# Adafruit_HUZZAH_ESP8266_Basic_Breakout.net
KiCad netlist of a schematic drawn in EAGLE
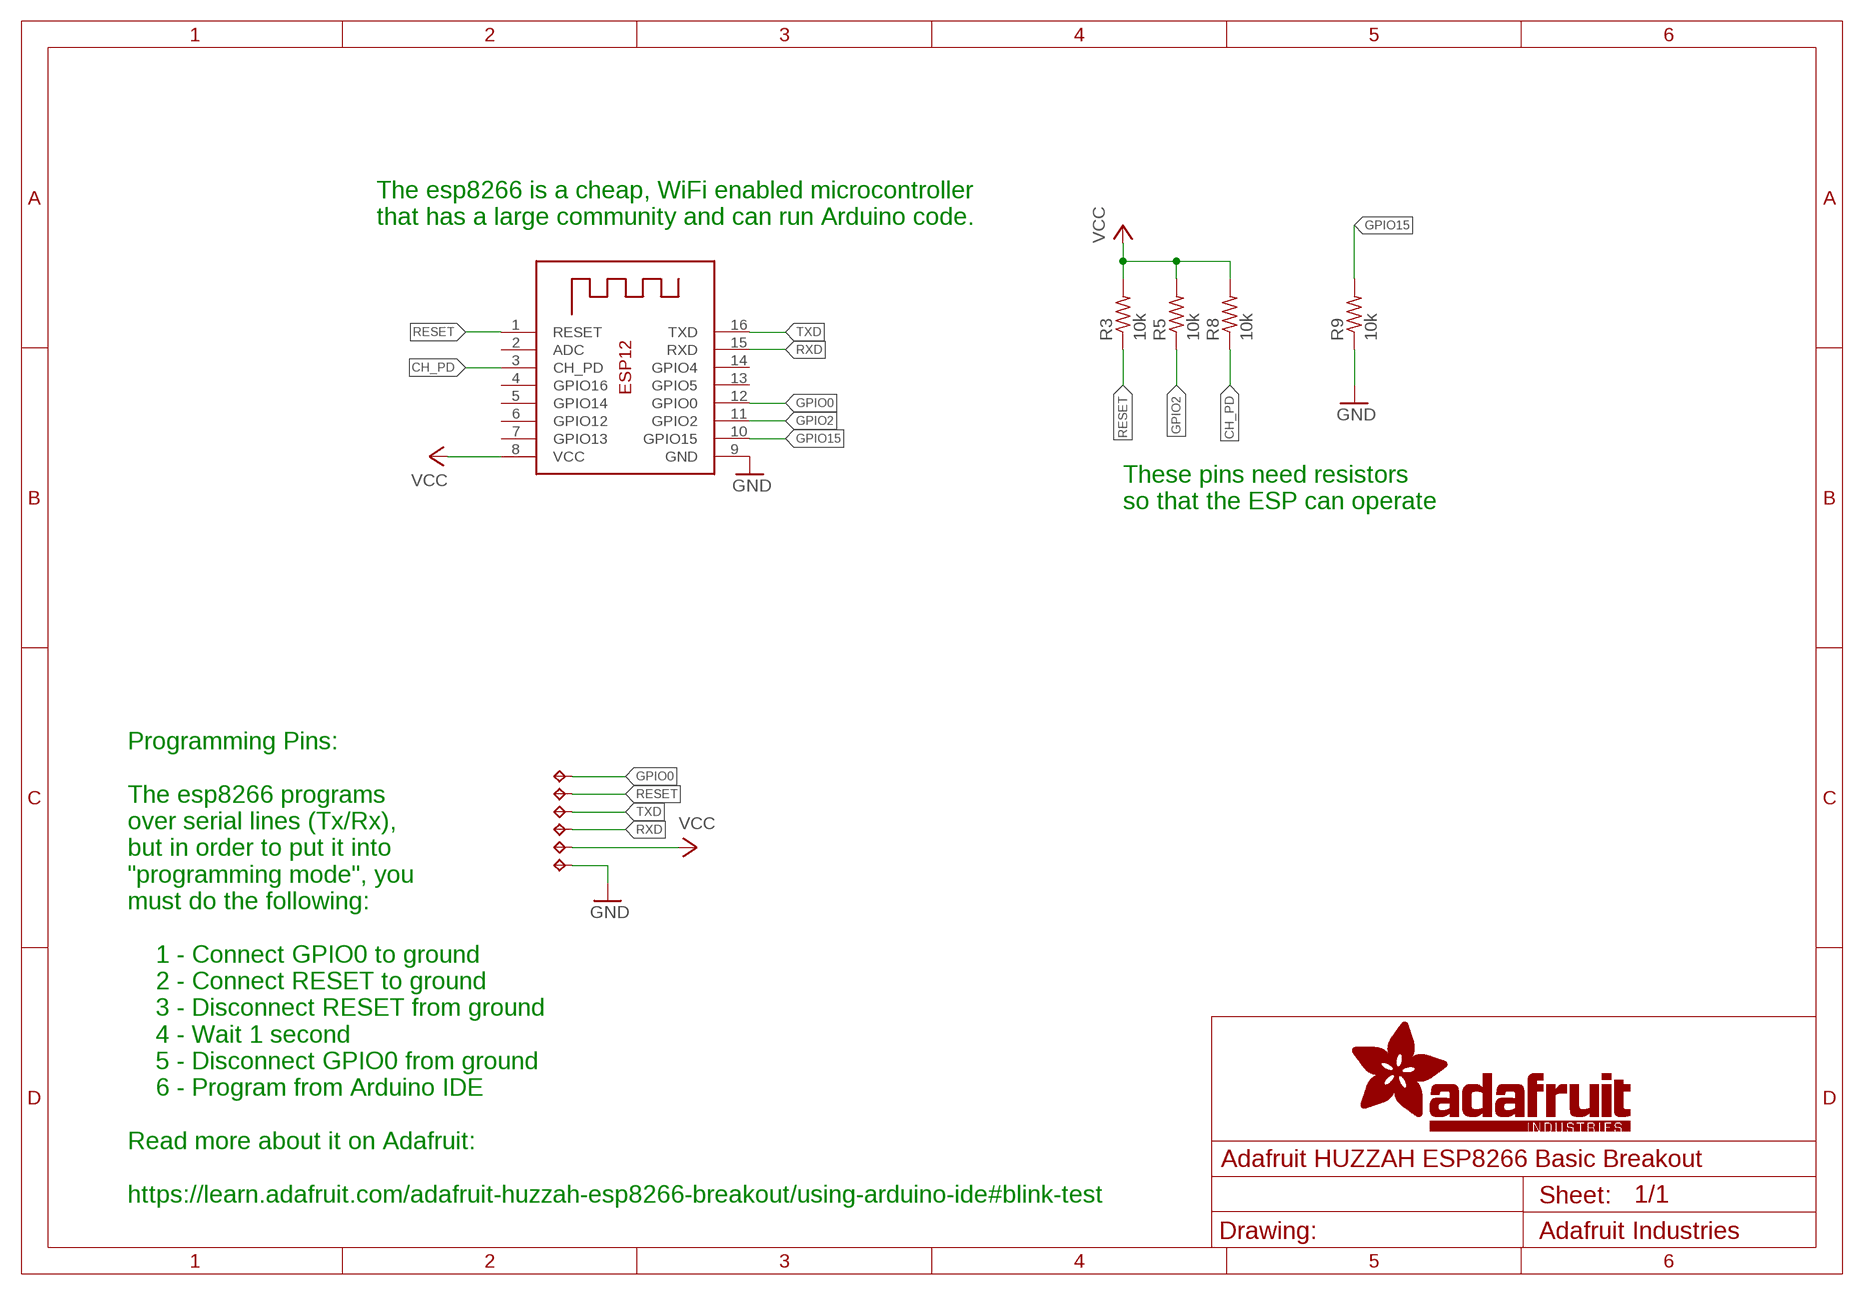
[diagram p0: schematic, sheet 1]

(export (version "E")
  (design (tool "Eeschema 10.0.6"))
  (components
    (comp (ref "GND")
      (value "TPTP20R")
      (footprint "eagle-import:TP20R")
      (libsource (lib "eagle-import") (part "TPTP20R"))
    )
    (comp (ref "GPIO0")
      (value "TPTP20R")
      (footprint "eagle-import:TP20R")
      (libsource (lib "eagle-import") (part "TPTP20R"))
    )
    (comp (ref "R3")
      (value "10k")
      (footprint "eagle-import:R0603")
      (libsource (lib "eagle-import") (part "R-US_R0603"))
    )
    (comp (ref "R5")
      (value "10k")
      (footprint "eagle-import:R0603")
      (libsource (lib "eagle-import") (part "R-US_R0603"))
    )
    (comp (ref "R8")
      (value "10k")
      (footprint "eagle-import:R0603")
      (libsource (lib "eagle-import") (part "R-US_R0603"))
    )
    (comp (ref "R9")
      (value "10k")
      (footprint "eagle-import:R0603")
      (libsource (lib "eagle-import") (part "R-US_R0603"))
    )
    (comp (ref "RESET")
      (value "TPTP20R")
      (footprint "eagle-import:TP20R")
      (libsource (lib "eagle-import") (part "TPTP20R"))
    )
    (comp (ref "RX")
      (value "TPTP20R")
      (footprint "eagle-import:TP20R")
      (libsource (lib "eagle-import") (part "TPTP20R"))
    )
    (comp (ref "TX")
      (value "TPTP20R")
      (footprint "eagle-import:TP20R")
      (libsource (lib "eagle-import") (part "TPTP20R"))
    )
    (comp (ref "VCC")
      (value "TPTP20R")
      (footprint "eagle-import:TP20R")
      (libsource (lib "eagle-import") (part "TPTP20R"))
    )
    (comp (ref "X1")
      (value "ESP-12")
      (footprint "eagle-import:ESP-12")
      (libsource (lib "eagle-import") (part "ESP-12"))
    )
  )
  (nets
    (net (code "1") (name "CH_PD") (class "Default")
      (node (ref "R8") (pin "1") (pinfunction "1_1") (pintype "passive"))
      (node (ref "X1") (pin "3") (pinfunction "CH_PD_3") (pintype "input"))
    )
    (net (code "2") (name "GND") (class "Default")
      (node (ref "GND") (pin "TP") (pinfunction "TP_TP") (pintype "input"))
      (node (ref "R9") (pin "1") (pinfunction "1_1") (pintype "passive"))
      (node (ref "X1") (pin "9") (pinfunction "GND_9") (pintype "power_in"))
    )
    (net (code "3") (name "GPIO0") (class "Default")
      (node (ref "GPIO0") (pin "TP") (pinfunction "TP_TP") (pintype "input"))
      (node (ref "X1") (pin "12") (pinfunction "GPIO0_12") (pintype "bidirectional"))
    )
    (net (code "4") (name "GPIO2") (class "Default")
      (node (ref "R5") (pin "1") (pinfunction "1_1") (pintype "passive"))
      (node (ref "X1") (pin "11") (pinfunction "GPIO2_11") (pintype "bidirectional"))
    )
    (net (code "5") (name "GPIO15") (class "Default")
      (node (ref "R9") (pin "2") (pinfunction "2_2") (pintype "passive"))
      (node (ref "X1") (pin "10") (pinfunction "GPIO15_10") (pintype "bidirectional"))
    )
    (net (code "6") (name "RESET") (class "Default")
      (node (ref "R3") (pin "1") (pinfunction "1_1") (pintype "passive"))
      (node (ref "RESET") (pin "TP") (pinfunction "TP_TP") (pintype "input"))
      (node (ref "X1") (pin "1") (pinfunction "RESET_1") (pintype "input"))
    )
    (net (code "7") (name "RXD") (class "Default")
      (node (ref "RX") (pin "TP") (pinfunction "TP_TP") (pintype "input"))
      (node (ref "X1") (pin "15") (pinfunction "RXD_15") (pintype "input"))
    )
    (net (code "8") (name "TXD") (class "Default")
      (node (ref "TX") (pin "TP") (pinfunction "TP_TP") (pintype "input"))
      (node (ref "X1") (pin "16") (pinfunction "TXD_16") (pintype "output"))
    )
    (net (code "9") (name "VCC") (class "Default")
      (node (ref "R3") (pin "2") (pinfunction "2_2") (pintype "passive"))
      (node (ref "R5") (pin "2") (pinfunction "2_2") (pintype "passive"))
      (node (ref "R8") (pin "2") (pinfunction "2_2") (pintype "passive"))
      (node (ref "VCC") (pin "TP") (pinfunction "TP_TP") (pintype "input"))
      (node (ref "X1") (pin "8") (pinfunction "VCC_8") (pintype "power_in"))
    )
    (net (code "10") (name "unconnected-(X1-ADC-Pad2)") (class "Default")
      (node (ref "X1") (pin "2") (pinfunction "ADC_2") (pintype "passive"))
    )
    (net (code "11") (name "unconnected-(X1-GPIO4-Pad14)") (class "Default")
      (node (ref "X1") (pin "14") (pinfunction "GPIO4_14") (pintype "bidirectional"))
    )
    (net (code "12") (name "unconnected-(X1-GPIO5-Pad13)") (class "Default")
      (node (ref "X1") (pin "13") (pinfunction "GPIO5_13") (pintype "bidirectional"))
    )
    (net (code "13") (name "unconnected-(X1-GPIO12-Pad6)") (class "Default")
      (node (ref "X1") (pin "6") (pinfunction "GPIO12_6") (pintype "bidirectional"))
    )
    (net (code "14") (name "unconnected-(X1-GPIO13-Pad7)") (class "Default")
      (node (ref "X1") (pin "7") (pinfunction "GPIO13_7") (pintype "bidirectional"))
    )
    (net (code "15") (name "unconnected-(X1-GPIO14-Pad5)") (class "Default")
      (node (ref "X1") (pin "5") (pinfunction "GPIO14_5") (pintype "bidirectional"))
    )
    (net (code "16") (name "unconnected-(X1-GPIO16-Pad4)") (class "Default")
      (node (ref "X1") (pin "4") (pinfunction "GPIO16_4") (pintype "bidirectional"))
    )
  )
)
